# STM32.net
KiCad netlist of a schematic drawn in Altium Designer
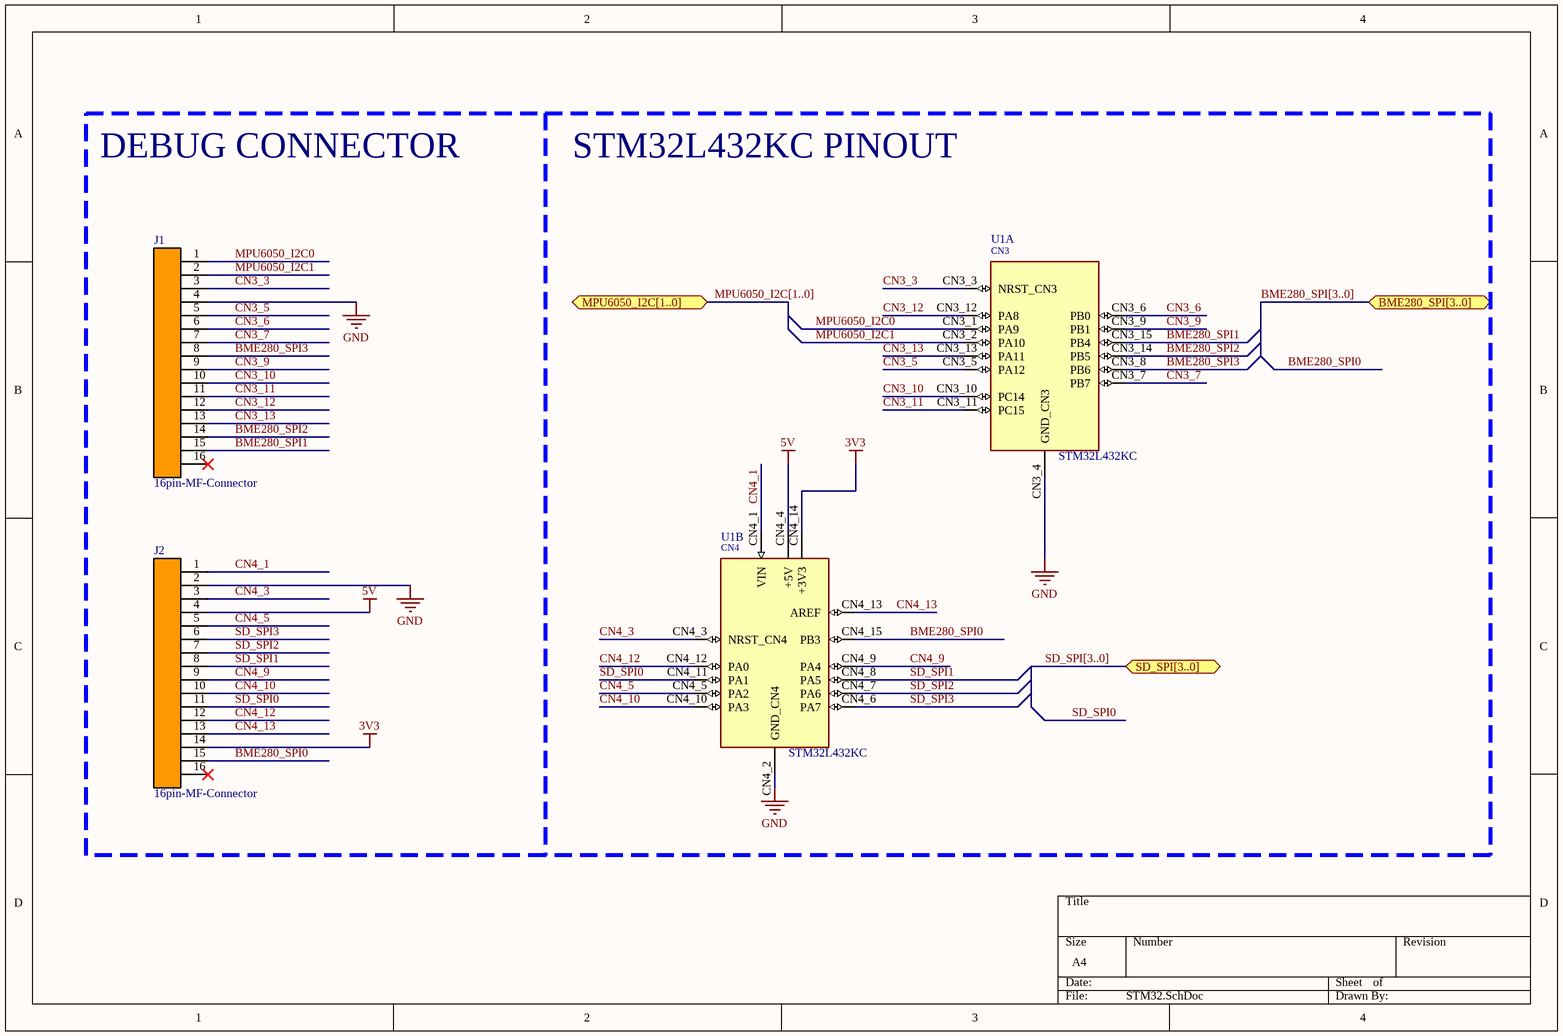
[diagram p0: STM32.SchDoc]

(export (version "E")
  (design (tool "Eeschema 10.0.6"))
  (components
    (comp (ref "J1")
      (value "16pin-MF-Connector")
      (footprint "16pin-MF-Connector")
      (libsource (lib "RocketLib") (part "16pin-MF-Connector"))
    )
    (comp (ref "J2")
      (value "16pin-MF-Connector")
      (footprint "16pin-MF-Connector")
      (libsource (lib "RocketLib") (part "16pin-MF-Connector"))
    )
    (comp (ref "U1")
      (value "STM32L432KC")
      (footprint "STM32L432KC")
      (libsource (lib "RocketLib") (part "STM32L432KC"))
    )
  )
  (nets
    (net (code "1") (name "/BME280_SPI0") (class "Default")
      (node (ref "J2") (pin "15") (pinfunction "15_15") (pintype "passive"))
      (node (ref "U1") (pin "CN4_15") (pinfunction "PB3_CN4_15") (pintype "bidirectional"))
    )
    (net (code "2") (name "/BME280_SPI1") (class "Default")
      (node (ref "J1") (pin "15") (pinfunction "15_15") (pintype "passive"))
      (node (ref "U1") (pin "CN3_15") (pinfunction "PB4_CN3_15") (pintype "bidirectional"))
    )
    (net (code "3") (name "/BME280_SPI2") (class "Default")
      (node (ref "J1") (pin "14") (pinfunction "14_14") (pintype "passive"))
      (node (ref "U1") (pin "CN3_14") (pinfunction "PB5_CN3_14") (pintype "bidirectional"))
    )
    (net (code "4") (name "/BME280_SPI3") (class "Default")
      (node (ref "J1") (pin "8") (pinfunction "8_8") (pintype "passive"))
      (node (ref "U1") (pin "CN3_8") (pinfunction "PB6_CN3_8") (pintype "bidirectional"))
    )
    (net (code "6") (name "/CN3_3") (class "Default")
      (node (ref "J1") (pin "3") (pinfunction "3_3") (pintype "passive"))
      (node (ref "U1") (pin "CN3_3") (pinfunction "NRST_CN3_CN3_3") (pintype "bidirectional"))
    )
    (net (code "7") (name "/CN3_5") (class "Default")
      (node (ref "J1") (pin "5") (pinfunction "5_5") (pintype "passive"))
      (node (ref "U1") (pin "CN3_5") (pinfunction "PA12_CN3_5") (pintype "bidirectional"))
    )
    (net (code "8") (name "/CN3_6") (class "Default")
      (node (ref "J1") (pin "6") (pinfunction "6_6") (pintype "passive"))
      (node (ref "U1") (pin "CN3_6") (pinfunction "PB0_CN3_6") (pintype "bidirectional"))
    )
    (net (code "9") (name "/CN3_7") (class "Default")
      (node (ref "J1") (pin "7") (pinfunction "7_7") (pintype "passive"))
      (node (ref "U1") (pin "CN3_7") (pinfunction "PB7_CN3_7") (pintype "bidirectional"))
    )
    (net (code "10") (name "/CN3_9") (class "Default")
      (node (ref "J1") (pin "9") (pinfunction "9_9") (pintype "passive"))
      (node (ref "U1") (pin "CN3_9") (pinfunction "PB1_CN3_9") (pintype "bidirectional"))
    )
    (net (code "11") (name "/CN3_10") (class "Default")
      (node (ref "J1") (pin "10") (pinfunction "10_10") (pintype "passive"))
      (node (ref "U1") (pin "CN3_10") (pinfunction "PC14_CN3_10") (pintype "bidirectional"))
    )
    (net (code "12") (name "/CN3_11") (class "Default")
      (node (ref "J1") (pin "11") (pinfunction "11_11") (pintype "passive"))
      (node (ref "U1") (pin "CN3_11") (pinfunction "PC15_CN3_11") (pintype "bidirectional"))
    )
    (net (code "13") (name "/CN3_12") (class "Default")
      (node (ref "J1") (pin "12") (pinfunction "12_12") (pintype "passive"))
      (node (ref "U1") (pin "CN3_12") (pinfunction "PA8_CN3_12") (pintype "bidirectional"))
    )
    (net (code "14") (name "/CN3_13") (class "Default")
      (node (ref "J1") (pin "13") (pinfunction "13_13") (pintype "passive"))
      (node (ref "U1") (pin "CN3_13") (pinfunction "PA11_CN3_13") (pintype "bidirectional"))
    )
    (net (code "15") (name "/CN4_1") (class "Default")
      (node (ref "J2") (pin "1") (pinfunction "1_1") (pintype "passive"))
      (node (ref "U1") (pin "CN4_1") (pinfunction "VIN_CN4_1") (pintype "input"))
    )
    (net (code "16") (name "/CN4_3") (class "Default")
      (node (ref "J2") (pin "3") (pinfunction "3_3") (pintype "passive"))
      (node (ref "U1") (pin "CN4_3") (pinfunction "NRST_CN4_CN4_3") (pintype "bidirectional"))
    )
    (net (code "17") (name "/CN4_5") (class "Default")
      (node (ref "J2") (pin "5") (pinfunction "5_5") (pintype "passive"))
      (node (ref "U1") (pin "CN4_5") (pinfunction "PA2_CN4_5") (pintype "bidirectional"))
    )
    (net (code "18") (name "/CN4_9") (class "Default")
      (node (ref "J2") (pin "9") (pinfunction "9_9") (pintype "passive"))
      (node (ref "U1") (pin "CN4_9") (pinfunction "PA4_CN4_9") (pintype "bidirectional"))
    )
    (net (code "19") (name "/CN4_10") (class "Default")
      (node (ref "J2") (pin "10") (pinfunction "10_10") (pintype "passive"))
      (node (ref "U1") (pin "CN4_10") (pinfunction "PA3_CN4_10") (pintype "bidirectional"))
    )
    (net (code "20") (name "/CN4_12") (class "Default")
      (node (ref "J2") (pin "12") (pinfunction "12_12") (pintype "passive"))
      (node (ref "U1") (pin "CN4_12") (pinfunction "PA0_CN4_12") (pintype "bidirectional"))
    )
    (net (code "21") (name "/CN4_13") (class "Default")
      (node (ref "J2") (pin "13") (pinfunction "13_13") (pintype "passive"))
      (node (ref "U1") (pin "CN4_13") (pinfunction "AREF_CN4_13") (pintype "bidirectional"))
    )
    (net (code "22") (name "/MPU6050_I2C0") (class "Default")
      (node (ref "J1") (pin "1") (pinfunction "1_1") (pintype "passive"))
      (node (ref "U1") (pin "CN3_1") (pinfunction "PA9_CN3_1") (pintype "bidirectional"))
    )
    (net (code "23") (name "/MPU6050_I2C1") (class "Default")
      (node (ref "J1") (pin "2") (pinfunction "2_2") (pintype "passive"))
      (node (ref "U1") (pin "CN3_2") (pinfunction "PA10_CN3_2") (pintype "bidirectional"))
    )
    (net (code "25") (name "/SD_SPI0") (class "Default")
      (node (ref "J2") (pin "11") (pinfunction "11_11") (pintype "passive"))
      (node (ref "U1") (pin "CN4_11") (pinfunction "PA1_CN4_11") (pintype "bidirectional"))
    )
    (net (code "26") (name "/SD_SPI1") (class "Default")
      (node (ref "J2") (pin "8") (pinfunction "8_8") (pintype "passive"))
      (node (ref "U1") (pin "CN4_8") (pinfunction "PA5_CN4_8") (pintype "bidirectional"))
    )
    (net (code "27") (name "/SD_SPI2") (class "Default")
      (node (ref "J2") (pin "7") (pinfunction "7_7") (pintype "passive"))
      (node (ref "U1") (pin "CN4_7") (pinfunction "PA6_CN4_7") (pintype "bidirectional"))
    )
    (net (code "28") (name "/SD_SPI3") (class "Default")
      (node (ref "J2") (pin "6") (pinfunction "6_6") (pintype "passive"))
      (node (ref "U1") (pin "CN4_6") (pinfunction "PA7_CN4_6") (pintype "bidirectional"))
    )
    (net (code "30") (name "3V3") (class "Default")
      (node (ref "J2") (pin "14") (pinfunction "14_14") (pintype "passive"))
      (node (ref "U1") (pin "CN4_14") (pinfunction "+3V3_CN4_14") (pintype "power_in"))
    )
    (net (code "31") (name "5V") (class "Default")
      (node (ref "J2") (pin "4") (pinfunction "4_4") (pintype "passive"))
      (node (ref "U1") (pin "CN4_4") (pinfunction "+5V_CN4_4") (pintype "power_in"))
    )
    (net (code "32") (name "GND") (class "Default")
      (node (ref "J1") (pin "4") (pinfunction "4_4") (pintype "passive"))
      (node (ref "J2") (pin "2") (pinfunction "2_2") (pintype "passive"))
      (node (ref "U1") (pin "CN3_4") (pinfunction "GND_CN3_CN3_4") (pintype "power_in"))
      (node (ref "U1") (pin "CN4_2") (pinfunction "GND_CN4_CN4_2") (pintype "power_in"))
    )
    (net (code "33") (name "unconnected-(J1-Pad16)") (class "Default")
      (node (ref "J1") (pin "16") (pinfunction "16_16") (pintype "passive+no_connect"))
    )
    (net (code "34") (name "unconnected-(J2-Pad16)") (class "Default")
      (node (ref "J2") (pin "16") (pinfunction "16_16") (pintype "passive+no_connect"))
    )
  )
)
